# homeboard1.net
KiCad netlist of a schematic drawn in EAGLE
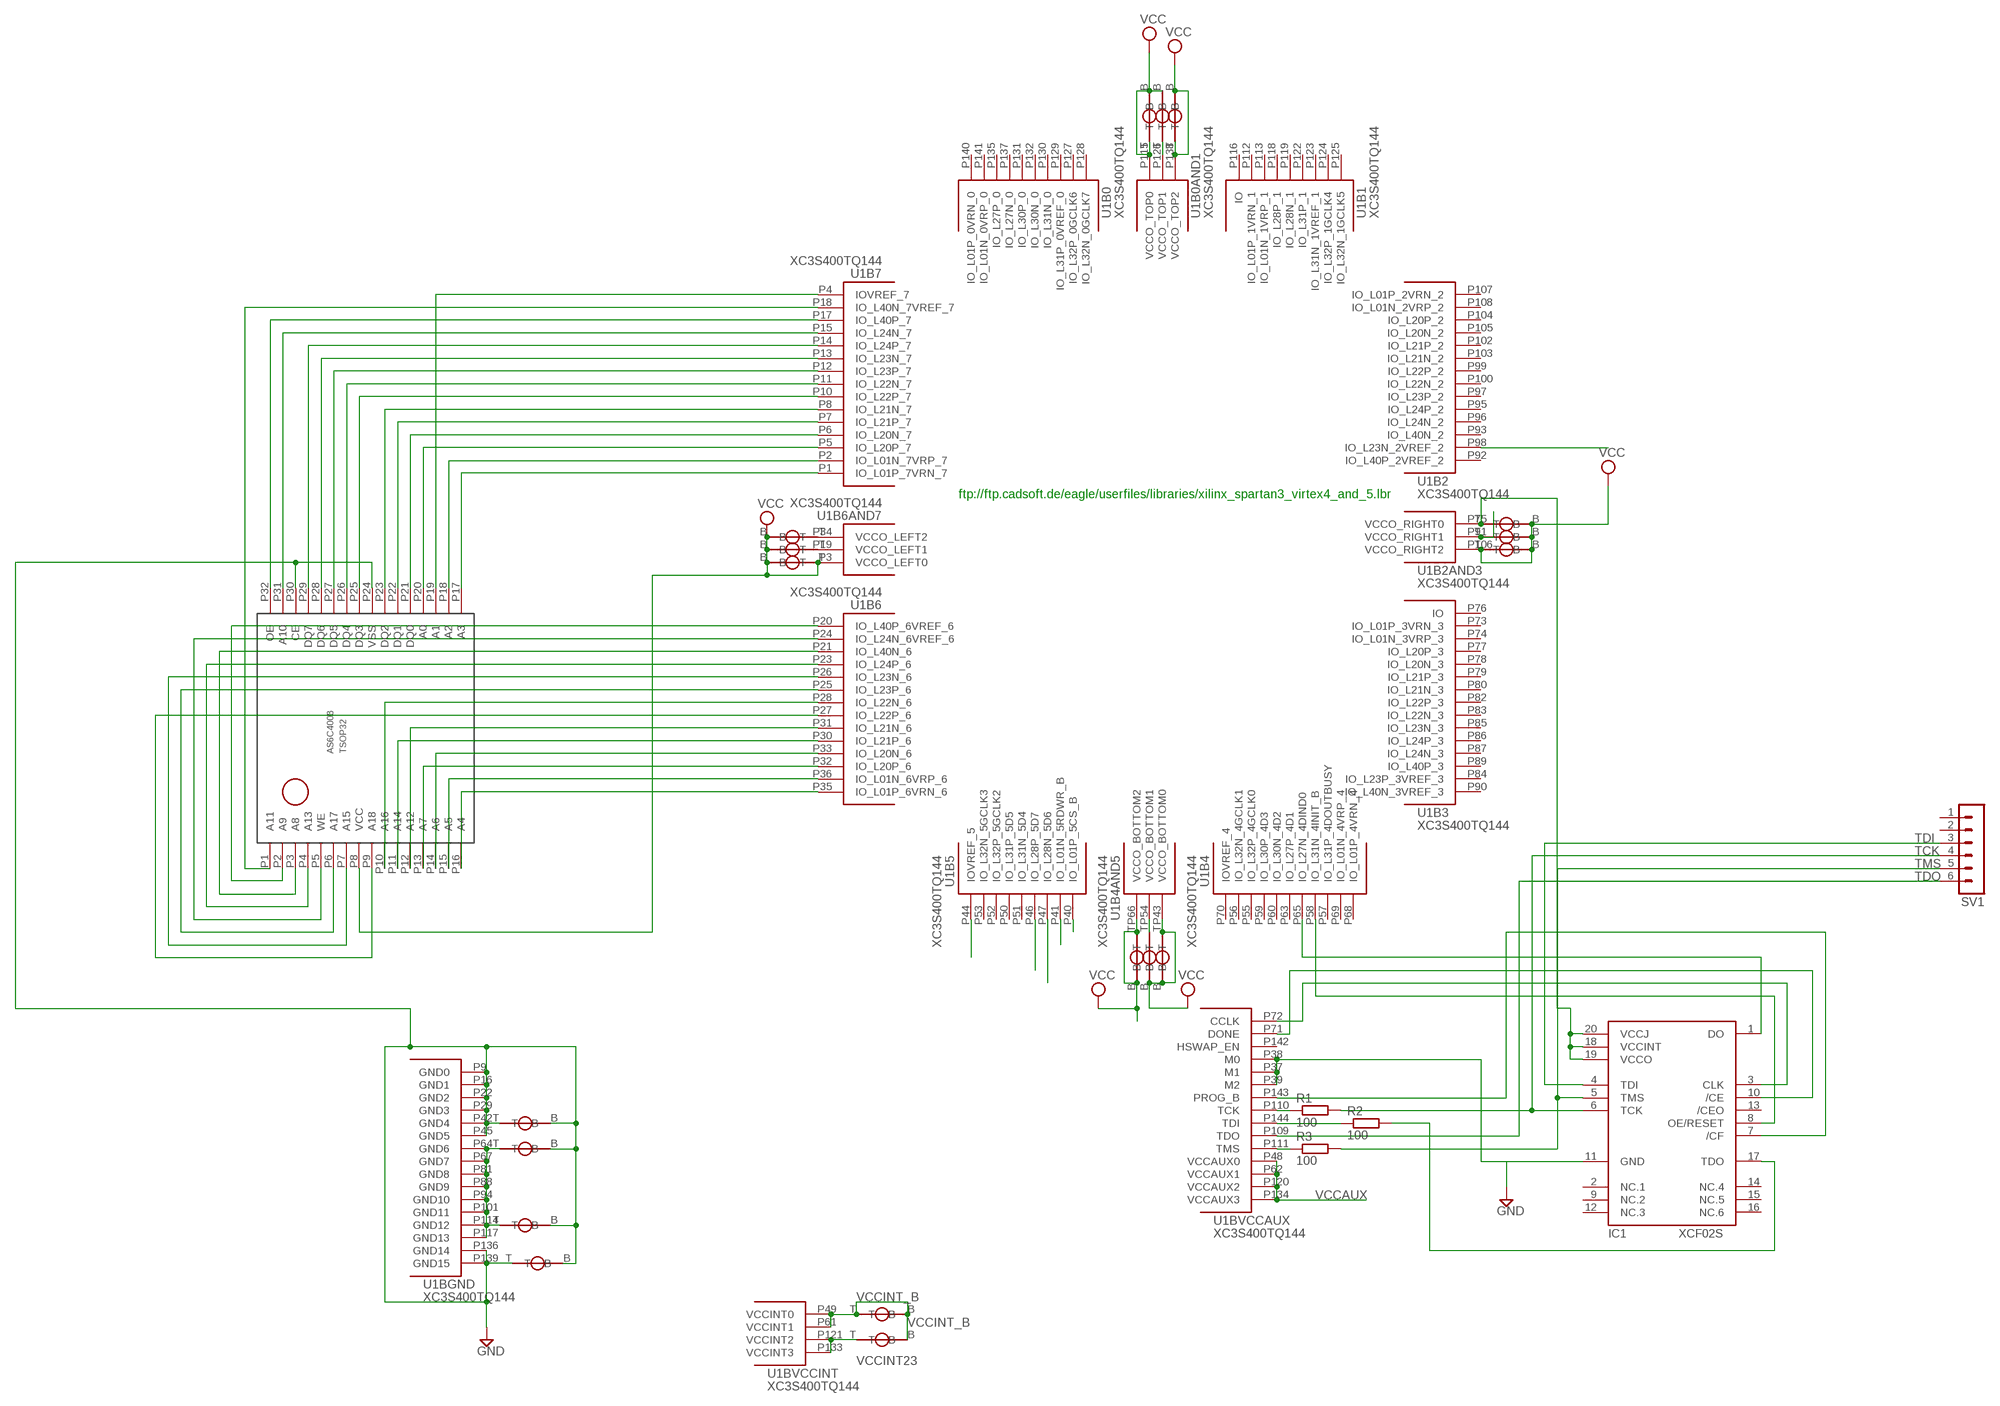
[diagram p0: schematic, sheet 1]

(export (version "E")
  (design (tool "Eeschema 10.0.6"))
  (components
    (comp (ref "IC1")
      (value "XCF02S")
      (footprint "eagle-import:VO20")
      (libsource (lib "eagle-import") (part "XCF02S"))
    )
    (comp (ref "R1")
      (value "100")
      (footprint "eagle-import:R0805")
      (libsource (lib "eagle-import") (part "R-EU_R0805"))
    )
    (comp (ref "R2")
      (value "100")
      (footprint "eagle-import:R0805")
      (libsource (lib "eagle-import") (part "R-EU_R0805"))
    )
    (comp (ref "R3")
      (value "100")
      (footprint "eagle-import:R0805")
      (libsource (lib "eagle-import") (part "R-EU_R0805"))
    )
    (comp (ref "SV1")
      (value "MA06-1")
      (footprint "eagle-import:MA06-1")
      (libsource (lib "eagle-import") (part "MA06-1"))
    )
    (comp (ref "U$1")
      (value "VIA_DIY")
      (footprint "eagle-import:VIA_DIY")
      (libsource (lib "eagle-import") (part "VIA_DIY"))
    )
    (comp (ref "U$2")
      (value "VIA_DIY")
      (footprint "eagle-import:VIA_DIY")
      (libsource (lib "eagle-import") (part "VIA_DIY"))
    )
    (comp (ref "U$3")
      (value "VIA_DIY")
      (footprint "eagle-import:VIA_DIY")
      (libsource (lib "eagle-import") (part "VIA_DIY"))
    )
    (comp (ref "U$4")
      (value "AS6C4008")
      (footprint "eagle-import:TSOP32")
      (libsource (lib "eagle-import") (part "AS6C4008"))
    )
    (comp (ref "U$5")
      (value "VIA_DIY")
      (footprint "eagle-import:VIA_DIY")
      (libsource (lib "eagle-import") (part "VIA_DIY"))
    )
    (comp (ref "U$6")
      (value "VIA_DIY")
      (footprint "eagle-import:VIA_DIY")
      (libsource (lib "eagle-import") (part "VIA_DIY"))
    )
    (comp (ref "U$7")
      (value "VIA_DIY")
      (footprint "eagle-import:VIA_DIY")
      (libsource (lib "eagle-import") (part "VIA_DIY"))
    )
    (comp (ref "U$10")
      (value "VIA_DIY")
      (footprint "eagle-import:VIA_DIY")
      (libsource (lib "eagle-import") (part "VIA_DIY"))
    )
    (comp (ref "U$14")
      (value "VIA_DIY")
      (footprint "eagle-import:VIA_DIY")
      (libsource (lib "eagle-import") (part "VIA_DIY"))
    )
    (comp (ref "U$15")
      (value "VIA_DIY")
      (footprint "eagle-import:VIA_DIY")
      (libsource (lib "eagle-import") (part "VIA_DIY"))
    )
    (comp (ref "U$18")
      (value "VIA_DIY")
      (footprint "eagle-import:VIA_DIY")
      (libsource (lib "eagle-import") (part "VIA_DIY"))
    )
    (comp (ref "U$19")
      (value "VIA_DIY")
      (footprint "eagle-import:VIA_DIY")
      (libsource (lib "eagle-import") (part "VIA_DIY"))
    )
    (comp (ref "U$20")
      (value "VIA_DIY")
      (footprint "eagle-import:VIA_DIY")
      (libsource (lib "eagle-import") (part "VIA_DIY"))
    )
    (comp (ref "U$23")
      (value "VIA_DIY")
      (footprint "eagle-import:VIA_DIY")
      (libsource (lib "eagle-import") (part "VIA_DIY"))
    )
    (comp (ref "U$25")
      (value "VIA_DIY")
      (footprint "eagle-import:VIA_DIY")
      (libsource (lib "eagle-import") (part "VIA_DIY"))
    )
    (comp (ref "U$26")
      (value "VIA_DIY")
      (footprint "eagle-import:VIA_DIY")
      (libsource (lib "eagle-import") (part "VIA_DIY"))
    )
    (comp (ref "U$27")
      (value "VIA_DIY")
      (footprint "eagle-import:VIA_DIY")
      (libsource (lib "eagle-import") (part "VIA_DIY"))
    )
    (comp (ref "U$28")
      (value "VIA_DIY")
      (footprint "eagle-import:VIA_DIY")
      (libsource (lib "eagle-import") (part "VIA_DIY"))
    )
    (comp (ref "U$29")
      (value "VIA_DIY")
      (footprint "eagle-import:VIA_DIY")
      (libsource (lib "eagle-import") (part "VIA_DIY"))
    )
    (comp (ref "U1")
      (value "XC3S400TQ144")
      (footprint "eagle-import:TQ144")
      (libsource (lib "eagle-import") (part "XC3S400TQ144"))
    )
  )
  (nets
    (net (code "1") (name "/TCK") (class "Default")
      (node (ref "IC1") (pin "6") (pinfunction "TCK_6") (pintype "bidirectional"))
      (node (ref "R1") (pin "2") (pinfunction "2_2") (pintype "passive"))
      (node (ref "SV1") (pin "4") (pinfunction "4_4") (pintype "passive"))
    )
    (net (code "2") (name "/TDI") (class "Default")
      (node (ref "IC1") (pin "4") (pinfunction "TDI_4") (pintype "bidirectional"))
      (node (ref "SV1") (pin "3") (pinfunction "3_3") (pintype "passive"))
    )
    (net (code "3") (name "/TDO") (class "Default")
      (node (ref "SV1") (pin "6") (pinfunction "6_6") (pintype "passive"))
      (node (ref "U1") (pin "P109") (pinfunction "TDO_P109") (pintype "bidirectional"))
    )
    (net (code "4") (name "/TMS") (class "Default")
      (node (ref "IC1") (pin "5") (pinfunction "TMS_5") (pintype "bidirectional"))
      (node (ref "R3") (pin "2") (pinfunction "2_2") (pintype "passive"))
      (node (ref "SV1") (pin "5") (pinfunction "5_5") (pintype "passive"))
    )
    (net (code "5") (name "/VCCAUX") (class "Default")
      (node (ref "U1") (pin "P120") (pinfunction "VCCAUX2_P120") (pintype "passive"))
      (node (ref "U1") (pin "P134") (pinfunction "VCCAUX3_P134") (pintype "passive"))
      (node (ref "U1") (pin "P48") (pinfunction "VCCAUX0_P48") (pintype "passive"))
      (node (ref "U1") (pin "P62") (pinfunction "VCCAUX1_P62") (pintype "passive"))
    )
    (net (code "6") (name "/VCCINT23") (class "Default")
      (node (ref "U$23") (pin "T") (pinfunction "T_T") (pintype "bidirectional"))
      (node (ref "U1") (pin "P121") (pinfunction "VCCINT2_P121") (pintype "passive"))
      (node (ref "U1") (pin "P133") (pinfunction "VCCINT3_P133") (pintype "passive"))
    )
    (net (code "7") (name "/VCCINT_B") (class "Default")
      (node (ref "U$1") (pin "B") (pinfunction "B_B") (pintype "bidirectional"))
      (node (ref "U$1") (pin "T") (pinfunction "T_T") (pintype "bidirectional"))
      (node (ref "U$23") (pin "B") (pinfunction "B_B") (pintype "bidirectional"))
      (node (ref "U1") (pin "P49") (pinfunction "VCCINT0_P49") (pintype "passive"))
      (node (ref "U1") (pin "P61") (pinfunction "VCCINT1_P61") (pintype "passive"))
    )
    (net (code "8") (name "GND") (class "Default")
      (node (ref "IC1") (pin "11") (pinfunction "GND_11") (pintype "bidirectional"))
      (node (ref "U$2") (pin "B") (pinfunction "B_B") (pintype "bidirectional"))
      (node (ref "U$20") (pin "B") (pinfunction "B_B") (pintype "bidirectional"))
      (node (ref "U$3") (pin "B") (pinfunction "B_B") (pintype "bidirectional"))
      (node (ref "U$3") (pin "T") (pinfunction "T_T") (pintype "bidirectional"))
      (node (ref "U$4") (pin "P24") (pinfunction "VSS_P24") (pintype "bidirectional"))
      (node (ref "U$4") (pin "P30") (pinfunction "CE_P30") (pintype "bidirectional"))
      (node (ref "U$5") (pin "B") (pinfunction "B_B") (pintype "bidirectional"))
      (node (ref "U$5") (pin "T") (pinfunction "T_T") (pintype "bidirectional"))
      (node (ref "U1") (pin "P136") (pinfunction "GND14_P136") (pintype "passive"))
      (node (ref "U1") (pin "P139") (pinfunction "GND15_P139") (pintype "passive"))
      (node (ref "U1") (pin "P16") (pinfunction "GND1_P16") (pintype "passive"))
      (node (ref "U1") (pin "P22") (pinfunction "GND2_P22") (pintype "passive"))
      (node (ref "U1") (pin "P29") (pinfunction "GND3_P29") (pintype "passive"))
      (node (ref "U1") (pin "P37") (pinfunction "M1_P37") (pintype "bidirectional"))
      (node (ref "U1") (pin "P38") (pinfunction "M0_P38") (pintype "bidirectional"))
      (node (ref "U1") (pin "P39") (pinfunction "M2_P39") (pintype "bidirectional"))
      (node (ref "U1") (pin "P42") (pinfunction "GND4_P42") (pintype "passive"))
      (node (ref "U1") (pin "P45") (pinfunction "GND5_P45") (pintype "passive"))
      (node (ref "U1") (pin "P9") (pinfunction "GND0_P9") (pintype "passive"))
    )
    (net (code "9") (name "Net-(IC1-CLK)") (class "Default")
      (node (ref "IC1") (pin "3") (pinfunction "CLK_3") (pintype "bidirectional"))
      (node (ref "U1") (pin "P72") (pinfunction "CCLK_P72") (pintype "bidirectional"))
    )
    (net (code "10") (name "Net-(IC1-DO)") (class "Default")
      (node (ref "IC1") (pin "1") (pinfunction "DO_1") (pintype "bidirectional"))
      (node (ref "U1") (pin "P65") (pinfunction "IO_L27N_4DIND0_P65") (pintype "bidirectional"))
    )
    (net (code "11") (name "Net-(IC1-OE{slash}RESET)") (class "Default")
      (node (ref "IC1") (pin "8") (pinfunction "OE/RESET_8") (pintype "bidirectional"))
      (node (ref "U1") (pin "P58") (pinfunction "IO_L31N_4INIT_B_P58") (pintype "bidirectional"))
    )
    (net (code "12") (name "Net-(IC1-TDO)") (class "Default")
      (node (ref "IC1") (pin "17") (pinfunction "TDO_17") (pintype "bidirectional"))
      (node (ref "R2") (pin "2") (pinfunction "2_2") (pintype "passive"))
    )
    (net (code "13") (name "Net-(IC1-VCCINT)") (class "Default")
      (node (ref "IC1") (pin "18") (pinfunction "VCCINT_18") (pintype "bidirectional"))
      (node (ref "IC1") (pin "19") (pinfunction "VCCO_19") (pintype "bidirectional"))
      (node (ref "IC1") (pin "20") (pinfunction "VCCJ_20") (pintype "bidirectional"))
      (node (ref "U$29") (pin "T") (pinfunction "T_T") (pintype "bidirectional"))
      (node (ref "U1") (pin "P75") (pinfunction "VCCO_RIGHT0_P75") (pintype "passive"))
    )
    (net (code "14") (name "Net-(IC1-{slash}CE)") (class "Default")
      (node (ref "IC1") (pin "10") (pinfunction "/CE_10") (pintype "bidirectional"))
      (node (ref "U1") (pin "P71") (pinfunction "DONE_P71") (pintype "bidirectional"))
    )
    (net (code "15") (name "Net-(IC1-{slash}CF)") (class "Default")
      (node (ref "IC1") (pin "7") (pinfunction "/CF_7") (pintype "bidirectional"))
      (node (ref "U1") (pin "P143") (pinfunction "PROG_B_P143") (pintype "bidirectional"))
    )
    (net (code "16") (name "Net-(U$4-A0)") (class "Default")
      (node (ref "U$4") (pin "P20") (pinfunction "A0_P20") (pintype "bidirectional"))
      (node (ref "U1") (pin "P5") (pinfunction "IO_L20P_7_P5") (pintype "bidirectional"))
    )
    (net (code "17") (name "Net-(U$4-A1)") (class "Default")
      (node (ref "U$4") (pin "P19") (pinfunction "A1_P19") (pintype "bidirectional"))
      (node (ref "U1") (pin "P4") (pinfunction "IOVREF_7_P4") (pintype "bidirectional"))
    )
    (net (code "18") (name "Net-(U$4-A2)") (class "Default")
      (node (ref "U$4") (pin "P18") (pinfunction "A2_P18") (pintype "bidirectional"))
      (node (ref "U1") (pin "P2") (pinfunction "IO_L01N_7VRP_7_P2") (pintype "bidirectional"))
    )
    (net (code "19") (name "Net-(U$4-A3)") (class "Default")
      (node (ref "U$4") (pin "P17") (pinfunction "A3_P17") (pintype "bidirectional"))
      (node (ref "U1") (pin "P1") (pinfunction "IO_L01P_7VRN_7_P1") (pintype "bidirectional"))
    )
    (net (code "20") (name "Net-(U$4-A4)") (class "Default")
      (node (ref "U$4") (pin "P16") (pinfunction "A4_P16") (pintype "bidirectional"))
      (node (ref "U1") (pin "P35") (pinfunction "IO_L01P_6VRN_6_P35") (pintype "bidirectional"))
    )
    (net (code "21") (name "Net-(U$4-A5)") (class "Default")
      (node (ref "U$4") (pin "P15") (pinfunction "A5_P15") (pintype "bidirectional"))
      (node (ref "U1") (pin "P36") (pinfunction "IO_L01N_6VRP_6_P36") (pintype "bidirectional"))
    )
    (net (code "22") (name "Net-(U$4-A6)") (class "Default")
      (node (ref "U$4") (pin "P14") (pinfunction "A6_P14") (pintype "bidirectional"))
      (node (ref "U1") (pin "P33") (pinfunction "IO_L20N_6_P33") (pintype "bidirectional"))
    )
    (net (code "23") (name "Net-(U$4-A7)") (class "Default")
      (node (ref "U$4") (pin "P13") (pinfunction "A7_P13") (pintype "bidirectional"))
      (node (ref "U1") (pin "P32") (pinfunction "IO_L20P_6_P32") (pintype "bidirectional"))
    )
    (net (code "24") (name "Net-(U$4-A8)") (class "Default")
      (node (ref "U$4") (pin "P3") (pinfunction "A8_P3") (pintype "bidirectional"))
      (node (ref "U1") (pin "P21") (pinfunction "IO_L40N_6_P21") (pintype "bidirectional"))
    )
    (net (code "25") (name "Net-(U$4-A9)") (class "Default")
      (node (ref "U$4") (pin "P2") (pinfunction "A9_P2") (pintype "bidirectional"))
      (node (ref "U1") (pin "P20") (pinfunction "IO_L40P_6VREF_6_P20") (pintype "bidirectional"))
    )
    (net (code "26") (name "Net-(U$4-A10)") (class "Default")
      (node (ref "U$4") (pin "P31") (pinfunction "A10_P31") (pintype "bidirectional"))
      (node (ref "U1") (pin "P15") (pinfunction "IO_L24N_7_P15") (pintype "bidirectional"))
    )
    (net (code "27") (name "Net-(U$4-A11)") (class "Default")
      (node (ref "U$4") (pin "P1") (pinfunction "A11_P1") (pintype "bidirectional"))
      (node (ref "U1") (pin "P18") (pinfunction "IO_L40N_7VREF_7_P18") (pintype "bidirectional"))
    )
    (net (code "28") (name "Net-(U$4-A12)") (class "Default")
      (node (ref "U$4") (pin "P12") (pinfunction "A12_P12") (pintype "bidirectional"))
      (node (ref "U1") (pin "P31") (pinfunction "IO_L21N_6_P31") (pintype "bidirectional"))
    )
    (net (code "29") (name "Net-(U$4-A13)") (class "Default")
      (node (ref "U$4") (pin "P4") (pinfunction "A13_P4") (pintype "bidirectional"))
      (node (ref "U1") (pin "P23") (pinfunction "IO_L24P_6_P23") (pintype "bidirectional"))
    )
    (net (code "30") (name "Net-(U$4-A14)") (class "Default")
      (node (ref "U$4") (pin "P11") (pinfunction "A14_P11") (pintype "bidirectional"))
      (node (ref "U1") (pin "P30") (pinfunction "IO_L21P_6_P30") (pintype "bidirectional"))
    )
    (net (code "31") (name "Net-(U$4-A15)") (class "Default")
      (node (ref "U$4") (pin "P7") (pinfunction "A15_P7") (pintype "bidirectional"))
      (node (ref "U1") (pin "P26") (pinfunction "IO_L23N_6_P26") (pintype "bidirectional"))
    )
    (net (code "32") (name "Net-(U$4-A16)") (class "Default")
      (node (ref "U$4") (pin "P10") (pinfunction "A16_P10") (pintype "bidirectional"))
      (node (ref "U1") (pin "P28") (pinfunction "IO_L22N_6_P28") (pintype "bidirectional"))
    )
    (net (code "33") (name "Net-(U$4-A17)") (class "Default")
      (node (ref "U$4") (pin "P6") (pinfunction "A17_P6") (pintype "bidirectional"))
      (node (ref "U1") (pin "P25") (pinfunction "IO_L23P_6_P25") (pintype "bidirectional"))
    )
    (net (code "34") (name "Net-(U$4-A18)") (class "Default")
      (node (ref "U$4") (pin "P9") (pinfunction "A18_P9") (pintype "bidirectional"))
      (node (ref "U1") (pin "P27") (pinfunction "IO_L22P_6_P27") (pintype "bidirectional"))
    )
    (net (code "35") (name "Net-(U$4-DQ0)") (class "Default")
      (node (ref "U$4") (pin "P21") (pinfunction "DQ0_P21") (pintype "bidirectional"))
      (node (ref "U1") (pin "P6") (pinfunction "IO_L20N_7_P6") (pintype "bidirectional"))
    )
    (net (code "36") (name "Net-(U$4-DQ1)") (class "Default")
      (node (ref "U$4") (pin "P22") (pinfunction "DQ1_P22") (pintype "bidirectional"))
      (node (ref "U1") (pin "P7") (pinfunction "IO_L21P_7_P7") (pintype "bidirectional"))
    )
    (net (code "37") (name "Net-(U$4-DQ2)") (class "Default")
      (node (ref "U$4") (pin "P23") (pinfunction "DQ2_P23") (pintype "bidirectional"))
      (node (ref "U1") (pin "P8") (pinfunction "IO_L21N_7_P8") (pintype "bidirectional"))
    )
    (net (code "38") (name "Net-(U$4-DQ3)") (class "Default")
      (node (ref "U$4") (pin "P25") (pinfunction "DQ3_P25") (pintype "bidirectional"))
      (node (ref "U1") (pin "P10") (pinfunction "IO_L22P_7_P10") (pintype "bidirectional"))
    )
    (net (code "39") (name "Net-(U$4-DQ4)") (class "Default")
      (node (ref "U$4") (pin "P26") (pinfunction "DQ4_P26") (pintype "bidirectional"))
      (node (ref "U1") (pin "P11") (pinfunction "IO_L22N_7_P11") (pintype "bidirectional"))
    )
    (net (code "40") (name "Net-(U$4-DQ5)") (class "Default")
      (node (ref "U$4") (pin "P27") (pinfunction "DQ5_P27") (pintype "bidirectional"))
      (node (ref "U1") (pin "P12") (pinfunction "IO_L23P_7_P12") (pintype "bidirectional"))
    )
    (net (code "41") (name "Net-(U$4-DQ6)") (class "Default")
      (node (ref "U$4") (pin "P28") (pinfunction "DQ6_P28") (pintype "bidirectional"))
      (node (ref "U1") (pin "P13") (pinfunction "IO_L23N_7_P13") (pintype "bidirectional"))
    )
    (net (code "42") (name "Net-(U$4-DQ7)") (class "Default")
      (node (ref "U$4") (pin "P29") (pinfunction "DQ7_P29") (pintype "bidirectional"))
      (node (ref "U1") (pin "P14") (pinfunction "IO_L24P_7_P14") (pintype "bidirectional"))
    )
    (net (code "43") (name "Net-(U$4-OE)") (class "Default")
      (node (ref "U$4") (pin "P32") (pinfunction "OE_P32") (pintype "bidirectional"))
      (node (ref "U1") (pin "P17") (pinfunction "IO_L40P_7_P17") (pintype "bidirectional"))
    )
    (net (code "44") (name "Net-(U$4-WE)") (class "Default")
      (node (ref "U$4") (pin "P5") (pinfunction "WE_P5") (pintype "bidirectional"))
      (node (ref "U1") (pin "P24") (pinfunction "IO_L24N_6VREF_6_P24") (pintype "bidirectional"))
    )
    (net (code "45") (name "Net-(U1B-VCCO_TOP1)") (class "Default")
      (node (ref "U$10") (pin "T") (pinfunction "T_T") (pintype "bidirectional"))
      (node (ref "U1") (pin "P126") (pinfunction "VCCO_TOP1_P126") (pintype "passive"))
    )
    (net (code "46") (name "Net-(U1E-VCCO_RIGHT1)") (class "Default")
      (node (ref "U$28") (pin "T") (pinfunction "T_T") (pintype "bidirectional"))
      (node (ref "U1") (pin "P91") (pinfunction "VCCO_RIGHT1_P91") (pintype "passive"))
    )
    (net (code "47") (name "Net-(U1H-VCCO_BOTTOM1)") (class "Default")
      (node (ref "U$25") (pin "T") (pinfunction "T_T") (pintype "bidirectional"))
      (node (ref "U1") (pin "P54") (pinfunction "VCCO_BOTTOM1_P54") (pintype "passive"))
    )
    (net (code "48") (name "Net-(U1K-VCCO_LEFT1)") (class "Default")
      (node (ref "U$15") (pin "T") (pinfunction "T_T") (pintype "bidirectional"))
      (node (ref "U1") (pin "P19") (pinfunction "VCCO_LEFT1_P19") (pintype "passive"))
    )
    (net (code "49") (name "Net-(U1K-VCCO_LEFT2)") (class "Default")
      (node (ref "U$14") (pin "T") (pinfunction "T_T") (pintype "bidirectional"))
      (node (ref "U1") (pin "P34") (pinfunction "VCCO_LEFT2_P34") (pintype "passive"))
    )
    (net (code "50") (name "Net-(U1M-GND10)") (class "Default")
      (node (ref "U$2") (pin "T") (pinfunction "T_T") (pintype "bidirectional"))
      (node (ref "U$20") (pin "T") (pinfunction "T_T") (pintype "bidirectional"))
      (node (ref "U1") (pin "P101") (pinfunction "GND11_P101") (pintype "passive"))
      (node (ref "U1") (pin "P114") (pinfunction "GND12_P114") (pintype "passive"))
      (node (ref "U1") (pin "P117") (pinfunction "GND13_P117") (pintype "passive"))
      (node (ref "U1") (pin "P64") (pinfunction "GND6_P64") (pintype "passive"))
      (node (ref "U1") (pin "P67") (pinfunction "GND7_P67") (pintype "passive"))
      (node (ref "U1") (pin "P81") (pinfunction "GND8_P81") (pintype "passive"))
      (node (ref "U1") (pin "P88") (pinfunction "GND9_P88") (pintype "passive"))
      (node (ref "U1") (pin "P94") (pinfunction "GND10_P94") (pintype "passive"))
    )
    (net (code "51") (name "Net-(U1N-TCK)") (class "Default")
      (node (ref "R1") (pin "1") (pinfunction "1_1") (pintype "passive"))
      (node (ref "U1") (pin "P110") (pinfunction "TCK_P110") (pintype "bidirectional"))
    )
    (net (code "52") (name "Net-(U1N-TDI)") (class "Default")
      (node (ref "R2") (pin "1") (pinfunction "1_1") (pintype "passive"))
      (node (ref "U1") (pin "P144") (pinfunction "TDI_P144") (pintype "bidirectional"))
    )
    (net (code "53") (name "Net-(U1N-TMS)") (class "Default")
      (node (ref "R3") (pin "1") (pinfunction "1_1") (pintype "passive"))
      (node (ref "U1") (pin "P111") (pinfunction "TMS_P111") (pintype "bidirectional"))
    )
    (net (code "54") (name "VCC") (class "Default")
      (node (ref "U$10") (pin "B") (pinfunction "B_B") (pintype "bidirectional"))
      (node (ref "U$14") (pin "B") (pinfunction "B_B") (pintype "bidirectional"))
      (node (ref "U$15") (pin "B") (pinfunction "B_B") (pintype "bidirectional"))
      (node (ref "U$18") (pin "B") (pinfunction "B_B") (pintype "bidirectional"))
      (node (ref "U$18") (pin "T") (pinfunction "T_T") (pintype "bidirectional"))
      (node (ref "U$19") (pin "B") (pinfunction "B_B") (pintype "bidirectional"))
      (node (ref "U$19") (pin "T") (pinfunction "T_T") (pintype "bidirectional"))
      (node (ref "U$25") (pin "B") (pinfunction "B_B") (pintype "bidirectional"))
      (node (ref "U$26") (pin "B") (pinfunction "B_B") (pintype "bidirectional"))
      (node (ref "U$26") (pin "T") (pinfunction "T_T") (pintype "bidirectional"))
      (node (ref "U$27") (pin "B") (pinfunction "B_B") (pintype "bidirectional"))
      (node (ref "U$27") (pin "T") (pinfunction "T_T") (pintype "bidirectional"))
      (node (ref "U$28") (pin "B") (pinfunction "B_B") (pintype "bidirectional"))
      (node (ref "U$29") (pin "B") (pinfunction "B_B") (pintype "bidirectional"))
      (node (ref "U$4") (pin "P8") (pinfunction "VCC_P8") (pintype "bidirectional"))
      (node (ref "U$6") (pin "B") (pinfunction "B_B") (pintype "bidirectional"))
      (node (ref "U$6") (pin "T") (pinfunction "T_T") (pintype "bidirectional"))
      (node (ref "U$7") (pin "B") (pinfunction "B_B") (pintype "bidirectional"))
      (node (ref "U$7") (pin "T") (pinfunction "T_T") (pintype "bidirectional"))
      (node (ref "U1") (pin "P106") (pinfunction "VCCO_RIGHT2_P106") (pintype "passive"))
      (node (ref "U1") (pin "P115") (pinfunction "VCCO_TOP0_P115") (pintype "passive"))
      (node (ref "U1") (pin "P138") (pinfunction "VCCO_TOP2_P138") (pintype "passive"))
      (node (ref "U1") (pin "P3") (pinfunction "VCCO_LEFT0_P3") (pintype "passive"))
      (node (ref "U1") (pin "P43") (pinfunction "VCCO_BOTTOM0_P43") (pintype "passive"))
      (node (ref "U1") (pin "P66") (pinfunction "VCCO_BOTTOM2_P66") (pintype "passive"))
    )
    (net (code "55") (name "unconnected-(IC1-NC.1-Pad2)") (class "Default")
      (node (ref "IC1") (pin "2") (pinfunction "NC.1_2") (pintype "bidirectional"))
    )
    (net (code "56") (name "unconnected-(IC1-NC.2-Pad9)") (class "Default")
      (node (ref "IC1") (pin "9") (pinfunction "NC.2_9") (pintype "bidirectional"))
    )
    (net (code "57") (name "unconnected-(IC1-NC.3-Pad12)") (class "Default")
      (node (ref "IC1") (pin "12") (pinfunction "NC.3_12") (pintype "bidirectional"))
    )
    (net (code "58") (name "unconnected-(IC1-NC.4-Pad14)") (class "Default")
      (node (ref "IC1") (pin "14") (pinfunction "NC.4_14") (pintype "bidirectional"))
    )
    (net (code "59") (name "unconnected-(IC1-NC.5-Pad15)") (class "Default")
      (node (ref "IC1") (pin "15") (pinfunction "NC.5_15") (pintype "bidirectional"))
    )
    (net (code "60") (name "unconnected-(IC1-NC.6-Pad16)") (class "Default")
      (node (ref "IC1") (pin "16") (pinfunction "NC.6_16") (pintype "bidirectional"))
    )
    (net (code "61") (name "unconnected-(IC1-{slash}CEO-Pad13)") (class "Default")
      (node (ref "IC1") (pin "13") (pinfunction "/CEO_13") (pintype "bidirectional"))
    )
    (net (code "62") (name "unconnected-(SV1-Pad1)") (class "Default")
      (node (ref "SV1") (pin "1") (pinfunction "1_1") (pintype "passive"))
    )
    (net (code "63") (name "unconnected-(SV1-Pad2)") (class "Default")
      (node (ref "SV1") (pin "2") (pinfunction "2_2") (pintype "passive"))
    )
    (net (code "64") (name "unconnected-(U1A-IO_L01N_0VRP_0-PadP141)") (class "Default")
      (node (ref "U1") (pin "P141") (pinfunction "IO_L01N_0VRP_0_P141") (pintype "bidirectional"))
    )
    (net (code "65") (name "unconnected-(U1A-IO_L01P_0VRN_0-PadP140)") (class "Default")
      (node (ref "U1") (pin "P140") (pinfunction "IO_L01P_0VRN_0_P140") (pintype "bidirectional"))
    )
    (net (code "66") (name "unconnected-(U1A-IO_L27N_0-PadP137)") (class "Default")
      (node (ref "U1") (pin "P137") (pinfunction "IO_L27N_0_P137") (pintype "bidirectional"))
    )
    (net (code "67") (name "unconnected-(U1A-IO_L27P_0-PadP135)") (class "Default")
      (node (ref "U1") (pin "P135") (pinfunction "IO_L27P_0_P135") (pintype "bidirectional"))
    )
    (net (code "68") (name "unconnected-(U1A-IO_L30N_0-PadP132)") (class "Default")
      (node (ref "U1") (pin "P132") (pinfunction "IO_L30N_0_P132") (pintype "bidirectional"))
    )
    (net (code "69") (name "unconnected-(U1A-IO_L30P_0-PadP131)") (class "Default")
      (node (ref "U1") (pin "P131") (pinfunction "IO_L30P_0_P131") (pintype "bidirectional"))
    )
    (net (code "70") (name "unconnected-(U1A-IO_L31N_0-PadP130)") (class "Default")
      (node (ref "U1") (pin "P130") (pinfunction "IO_L31N_0_P130") (pintype "bidirectional"))
    )
    (net (code "71") (name "unconnected-(U1A-IO_L31P_0VREF_0-PadP129)") (class "Default")
      (node (ref "U1") (pin "P129") (pinfunction "IO_L31P_0VREF_0_P129") (pintype "bidirectional"))
    )
    (net (code "72") (name "unconnected-(U1A-IO_L32N_0GCLK7-PadP128)") (class "Default")
      (node (ref "U1") (pin "P128") (pinfunction "IO_L32N_0GCLK7_P128") (pintype "bidirectional"))
    )
    (net (code "73") (name "unconnected-(U1A-IO_L32P_0GCLK6-PadP127)") (class "Default")
      (node (ref "U1") (pin "P127") (pinfunction "IO_L32P_0GCLK6_P127") (pintype "bidirectional"))
    )
    (net (code "74") (name "unconnected-(U1C-IO-PadP116)") (class "Default")
      (node (ref "U1") (pin "P116") (pinfunction "IO_P116") (pintype "bidirectional"))
    )
    (net (code "75") (name "unconnected-(U1C-IO_L01N_1VRP_1-PadP113)") (class "Default")
      (node (ref "U1") (pin "P113") (pinfunction "IO_L01N_1VRP_1_P113") (pintype "bidirectional"))
    )
    (net (code "76") (name "unconnected-(U1C-IO_L01P_1VRN_1-PadP112)") (class "Default")
      (node (ref "U1") (pin "P112") (pinfunction "IO_L01P_1VRN_1_P112") (pintype "bidirectional"))
    )
    (net (code "77") (name "unconnected-(U1C-IO_L28N_1-PadP119)") (class "Default")
      (node (ref "U1") (pin "P119") (pinfunction "IO_L28N_1_P119") (pintype "bidirectional"))
    )
    (net (code "78") (name "unconnected-(U1C-IO_L28P_1-PadP118)") (class "Default")
      (node (ref "U1") (pin "P118") (pinfunction "IO_L28P_1_P118") (pintype "bidirectional"))
    )
    (net (code "79") (name "unconnected-(U1C-IO_L31N_1VREF_1-PadP123)") (class "Default")
      (node (ref "U1") (pin "P123") (pinfunction "IO_L31N_1VREF_1_P123") (pintype "bidirectional"))
    )
    (net (code "80") (name "unconnected-(U1C-IO_L31P_1-PadP122)") (class "Default")
      (node (ref "U1") (pin "P122") (pinfunction "IO_L31P_1_P122") (pintype "bidirectional"))
    )
    (net (code "81") (name "unconnected-(U1C-IO_L32N_1GCLK5-PadP125)") (class "Default")
      (node (ref "U1") (pin "P125") (pinfunction "IO_L32N_1GCLK5_P125") (pintype "bidirectional"))
    )
    (net (code "82") (name "unconnected-(U1C-IO_L32P_1GCLK4-PadP124)") (class "Default")
      (node (ref "U1") (pin "P124") (pinfunction "IO_L32P_1GCLK4_P124") (pintype "bidirectional"))
    )
    (net (code "83") (name "unconnected-(U1D-IO_L01N_2VRP_2-PadP108)") (class "Default")
      (node (ref "U1") (pin "P108") (pinfunction "IO_L01N_2VRP_2_P108") (pintype "bidirectional"))
    )
    (net (code "84") (name "unconnected-(U1D-IO_L01P_2VRN_2-PadP107)") (class "Default")
      (node (ref "U1") (pin "P107") (pinfunction "IO_L01P_2VRN_2_P107") (pintype "bidirectional"))
    )
    (net (code "85") (name "unconnected-(U1D-IO_L20N_2-PadP105)") (class "Default")
      (node (ref "U1") (pin "P105") (pinfunction "IO_L20N_2_P105") (pintype "bidirectional"))
    )
    (net (code "86") (name "unconnected-(U1D-IO_L20P_2-PadP104)") (class "Default")
      (node (ref "U1") (pin "P104") (pinfunction "IO_L20P_2_P104") (pintype "bidirectional"))
    )
    (net (code "87") (name "unconnected-(U1D-IO_L21N_2-PadP103)") (class "Default")
      (node (ref "U1") (pin "P103") (pinfunction "IO_L21N_2_P103") (pintype "bidirectional"))
    )
    (net (code "88") (name "unconnected-(U1D-IO_L21P_2-PadP102)") (class "Default")
      (node (ref "U1") (pin "P102") (pinfunction "IO_L21P_2_P102") (pintype "bidirectional"))
    )
    (net (code "89") (name "unconnected-(U1D-IO_L22N_2-PadP100)") (class "Default")
      (node (ref "U1") (pin "P100") (pinfunction "IO_L22N_2_P100") (pintype "bidirectional"))
    )
    (net (code "90") (name "unconnected-(U1D-IO_L22P_2-PadP99)") (class "Default")
      (node (ref "U1") (pin "P99") (pinfunction "IO_L22P_2_P99") (pintype "bidirectional"))
    )
    (net (code "91") (name "unconnected-(U1D-IO_L23N_2VREF_2-PadP98)") (class "Default")
      (node (ref "U1") (pin "P98") (pinfunction "IO_L23N_2VREF_2_P98") (pintype "bidirectional"))
    )
    (net (code "92") (name "unconnected-(U1D-IO_L23P_2-PadP97)") (class "Default")
      (node (ref "U1") (pin "P97") (pinfunction "IO_L23P_2_P97") (pintype "bidirectional"))
    )
    (net (code "93") (name "unconnected-(U1D-IO_L24N_2-PadP96)") (class "Default")
      (node (ref "U1") (pin "P96") (pinfunction "IO_L24N_2_P96") (pintype "bidirectional"))
    )
    (net (code "94") (name "unconnected-(U1D-IO_L24P_2-PadP95)") (class "Default")
      (node (ref "U1") (pin "P95") (pinfunction "IO_L24P_2_P95") (pintype "bidirectional"))
    )
    (net (code "95") (name "unconnected-(U1D-IO_L40N_2-PadP93)") (class "Default")
      (node (ref "U1") (pin "P93") (pinfunction "IO_L40N_2_P93") (pintype "bidirectional"))
    )
    (net (code "96") (name "unconnected-(U1D-IO_L40P_2VREF_2-PadP92)") (class "Default")
      (node (ref "U1") (pin "P92") (pinfunction "IO_L40P_2VREF_2_P92") (pintype "bidirectional"))
    )
    (net (code "97") (name "unconnected-(U1F-IO-PadP76)") (class "Default")
      (node (ref "U1") (pin "P76") (pinfunction "IO_P76") (pintype "bidirectional"))
    )
    (net (code "98") (name "unconnected-(U1F-IO_L01N_3VRP_3-PadP74)") (class "Default")
      (node (ref "U1") (pin "P74") (pinfunction "IO_L01N_3VRP_3_P74") (pintype "bidirectional"))
    )
    (net (code "99") (name "unconnected-(U1F-IO_L01P_3VRN_3-PadP73)") (class "Default")
      (node (ref "U1") (pin "P73") (pinfunction "IO_L01P_3VRN_3_P73") (pintype "bidirectional"))
    )
    (net (code "100") (name "unconnected-(U1F-IO_L20N_3-PadP78)") (class "Default")
      (node (ref "U1") (pin "P78") (pinfunction "IO_L20N_3_P78") (pintype "bidirectional"))
    )
    (net (code "101") (name "unconnected-(U1F-IO_L20P_3-PadP77)") (class "Default")
      (node (ref "U1") (pin "P77") (pinfunction "IO_L20P_3_P77") (pintype "bidirectional"))
    )
    (net (code "102") (name "unconnected-(U1F-IO_L21N_3-PadP80)") (class "Default")
      (node (ref "U1") (pin "P80") (pinfunction "IO_L21N_3_P80") (pintype "bidirectional"))
    )
    (net (code "103") (name "unconnected-(U1F-IO_L21P_3-PadP79)") (class "Default")
      (node (ref "U1") (pin "P79") (pinfunction "IO_L21P_3_P79") (pintype "bidirectional"))
    )
    (net (code "104") (name "unconnected-(U1F-IO_L22N_3-PadP83)") (class "Default")
      (node (ref "U1") (pin "P83") (pinfunction "IO_L22N_3_P83") (pintype "bidirectional"))
    )
    (net (code "105") (name "unconnected-(U1F-IO_L22P_3-PadP82)") (class "Default")
      (node (ref "U1") (pin "P82") (pinfunction "IO_L22P_3_P82") (pintype "bidirectional"))
    )
    (net (code "106") (name "unconnected-(U1F-IO_L23N_3-PadP85)") (class "Default")
      (node (ref "U1") (pin "P85") (pinfunction "IO_L23N_3_P85") (pintype "bidirectional"))
    )
    (net (code "107") (name "unconnected-(U1F-IO_L23P_3VREF_3-PadP84)") (class "Default")
      (node (ref "U1") (pin "P84") (pinfunction "IO_L23P_3VREF_3_P84") (pintype "bidirectional"))
    )
    (net (code "108") (name "unconnected-(U1F-IO_L24N_3-PadP87)") (class "Default")
      (node (ref "U1") (pin "P87") (pinfunction "IO_L24N_3_P87") (pintype "bidirectional"))
    )
    (net (code "109") (name "unconnected-(U1F-IO_L24P_3-PadP86)") (class "Default")
      (node (ref "U1") (pin "P86") (pinfunction "IO_L24P_3_P86") (pintype "bidirectional"))
    )
    (net (code "110") (name "unconnected-(U1F-IO_L40N_3VREF_3-PadP90)") (class "Default")
      (node (ref "U1") (pin "P90") (pinfunction "IO_L40N_3VREF_3_P90") (pintype "bidirectional"))
    )
    (net (code "111") (name "unconnected-(U1F-IO_L40P_3-PadP89)") (class "Default")
      (node (ref "U1") (pin "P89") (pinfunction "IO_L40P_3_P89") (pintype "bidirectional"))
    )
    (net (code "112") (name "unconnected-(U1G-IOVREF_4-PadP70)") (class "Default")
      (node (ref "U1") (pin "P70") (pinfunction "IOVREF_4_P70") (pintype "bidirectional"))
    )
    (net (code "113") (name "unconnected-(U1G-IO_L01N_4VRP_4-PadP69)") (class "Default")
      (node (ref "U1") (pin "P69") (pinfunction "IO_L01N_4VRP_4_P69") (pintype "bidirectional"))
    )
    (net (code "114") (name "unconnected-(U1G-IO_L01P_4VRN_4-PadP68)") (class "Default")
      (node (ref "U1") (pin "P68") (pinfunction "IO_L01P_4VRN_4_P68") (pintype "bidirectional"))
    )
    (net (code "115") (name "unconnected-(U1G-IO_L27P_4D1-PadP63)") (class "Default")
      (node (ref "U1") (pin "P63") (pinfunction "IO_L27P_4D1_P63") (pintype "bidirectional"))
    )
    (net (code "116") (name "unconnected-(U1G-IO_L30N_4D2-PadP60)") (class "Default")
      (node (ref "U1") (pin "P60") (pinfunction "IO_L30N_4D2_P60") (pintype "bidirectional"))
    )
    (net (code "117") (name "unconnected-(U1G-IO_L30P_4D3-PadP59)") (class "Default")
      (node (ref "U1") (pin "P59") (pinfunction "IO_L30P_4D3_P59") (pintype "bidirectional"))
    )
    (net (code "118") (name "unconnected-(U1G-IO_L31P_4DOUTBUSY-PadP57)") (class "Default")
      (node (ref "U1") (pin "P57") (pinfunction "IO_L31P_4DOUTBUSY_P57") (pintype "bidirectional"))
    )
    (net (code "119") (name "unconnected-(U1G-IO_L32N_4GCLK1-PadP56)") (class "Default")
      (node (ref "U1") (pin "P56") (pinfunction "IO_L32N_4GCLK1_P56") (pintype "bidirectional"))
    )
    (net (code "120") (name "unconnected-(U1G-IO_L32P_4GCLK0-PadP55)") (class "Default")
      (node (ref "U1") (pin "P55") (pinfunction "IO_L32P_4GCLK0_P55") (pintype "bidirectional"))
    )
    (net (code "121") (name "unconnected-(U1I-IOVREF_5-PadP44)") (class "Default")
      (node (ref "U1") (pin "P44") (pinfunction "IOVREF_5_P44") (pintype "bidirectional"))
    )
    (net (code "122") (name "unconnected-(U1I-IO_L01N_5RDWR_B-PadP41)") (class "Default")
      (node (ref "U1") (pin "P41") (pinfunction "IO_L01N_5RDWR_B_P41") (pintype "bidirectional"))
    )
    (net (code "123") (name "unconnected-(U1I-IO_L01P_5CS_B-PadP40)") (class "Default")
      (node (ref "U1") (pin "P40") (pinfunction "IO_L01P_5CS_B_P40") (pintype "bidirectional"))
    )
    (net (code "124") (name "unconnected-(U1I-IO_L28N_5D6-PadP47)") (class "Default")
      (node (ref "U1") (pin "P47") (pinfunction "IO_L28N_5D6_P47") (pintype "bidirectional"))
    )
    (net (code "125") (name "unconnected-(U1I-IO_L28P_5D7-PadP46)") (class "Default")
      (node (ref "U1") (pin "P46") (pinfunction "IO_L28P_5D7_P46") (pintype "bidirectional"))
    )
    (net (code "126") (name "unconnected-(U1I-IO_L31N_5D4-PadP51)") (class "Default")
      (node (ref "U1") (pin "P51") (pinfunction "IO_L31N_5D4_P51") (pintype "bidirectional"))
    )
    (net (code "127") (name "unconnected-(U1I-IO_L31P_5D5-PadP50)") (class "Default")
      (node (ref "U1") (pin "P50") (pinfunction "IO_L31P_5D5_P50") (pintype "bidirectional"))
    )
    (net (code "128") (name "unconnected-(U1I-IO_L32N_5GCLK3-PadP53)") (class "Default")
      (node (ref "U1") (pin "P53") (pinfunction "IO_L32N_5GCLK3_P53") (pintype "bidirectional"))
    )
    (net (code "129") (name "unconnected-(U1I-IO_L32P_5GCLK2-PadP52)") (class "Default")
      (node (ref "U1") (pin "P52") (pinfunction "IO_L32P_5GCLK2_P52") (pintype "bidirectional"))
    )
    (net (code "130") (name "unconnected-(U1N-HSWAP_EN-PadP142)") (class "Default")
      (node (ref "U1") (pin "P142") (pinfunction "HSWAP_EN_P142") (pintype "bidirectional"))
    )
  )
)
